# ConFLiCTuino.net
KiCad netlist of a schematic drawn in EAGLE
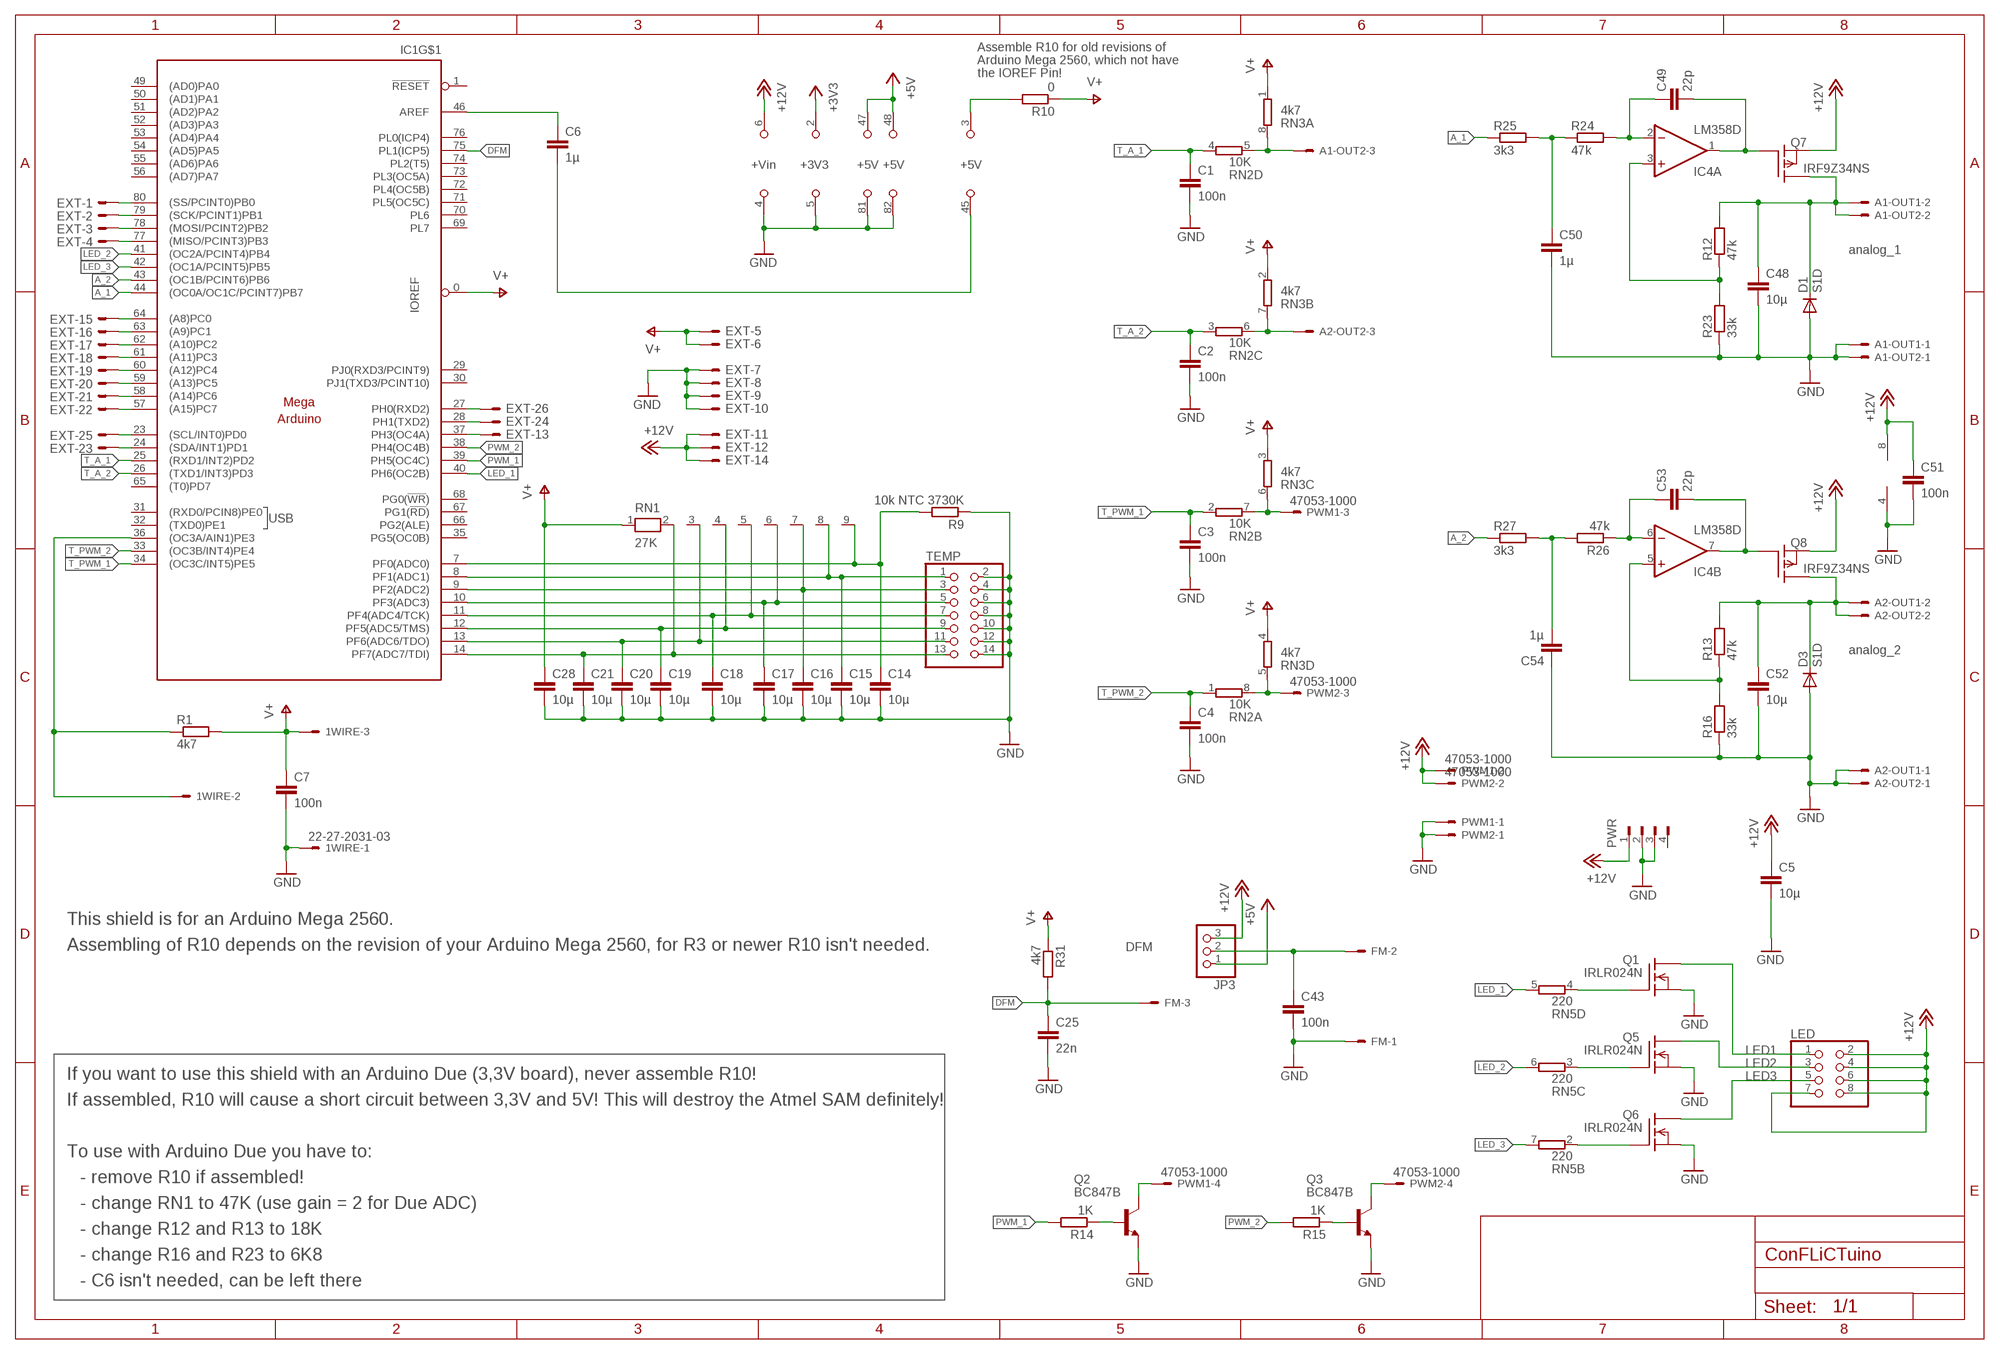
[diagram p0: schematic, sheet 1]

(export (version "E")
  (design (tool "Eeschema 10.0.6"))
  (components
    (comp (ref "1WIRE")
      (value "22-27-2031-03")
      (footprint "eagle-import:6410-03")
      (libsource (lib "eagle-import") (part "22-?-0327-2031"))
    )
    (comp (ref "A1-OUT1")
      (value "22-27-2031-03")
      (footprint "eagle-import:6410-03")
      (libsource (lib "eagle-import") (part "22-?-0327-2031"))
    )
    (comp (ref "A1-OUT2")
      (value "22-27-2031-03")
      (footprint "eagle-import:6410-03")
      (libsource (lib "eagle-import") (part "22-?-0327-2031"))
    )
    (comp (ref "A2-OUT1")
      (value "22-27-2031-03")
      (footprint "eagle-import:6410-03")
      (libsource (lib "eagle-import") (part "22-?-0327-2031"))
    )
    (comp (ref "A2-OUT2")
      (value "22-27-2031-03")
      (footprint "eagle-import:6410-03")
      (libsource (lib "eagle-import") (part "22-?-0327-2031"))
    )
    (comp (ref "C1")
      (value "100n")
      (footprint "eagle-import:C0805K")
      (libsource (lib "eagle-import") (part "C-EUC0805K"))
    )
    (comp (ref "C2")
      (value "100n")
      (footprint "eagle-import:C0805K")
      (libsource (lib "eagle-import") (part "C-EUC0805K"))
    )
    (comp (ref "C3")
      (value "100n")
      (footprint "eagle-import:C0805K")
      (libsource (lib "eagle-import") (part "C-EUC0805K"))
    )
    (comp (ref "C4")
      (value "100n")
      (footprint "eagle-import:C0805K")
      (libsource (lib "eagle-import") (part "C-EUC0805K"))
    )
    (comp (ref "C5")
      (value "10µ")
      (footprint "eagle-import:C0805K")
      (libsource (lib "eagle-import") (part "C-EUC0805K"))
    )
    (comp (ref "C6")
      (value "1µ")
      (footprint "eagle-import:C0805K")
      (libsource (lib "eagle-import") (part "C-EUC0805K"))
    )
    (comp (ref "C7")
      (value "100n")
      (footprint "eagle-import:C0805K")
      (libsource (lib "eagle-import") (part "C-EUC0805K"))
    )
    (comp (ref "C14")
      (value "10µ")
      (footprint "eagle-import:C0805K")
      (libsource (lib "eagle-import") (part "C-EUC0805K"))
    )
    (comp (ref "C15")
      (value "10µ")
      (footprint "eagle-import:C0805K")
      (libsource (lib "eagle-import") (part "C-EUC0805K"))
    )
    (comp (ref "C16")
      (value "10µ")
      (footprint "eagle-import:C0805K")
      (libsource (lib "eagle-import") (part "C-EUC0805K"))
    )
    (comp (ref "C17")
      (value "10µ")
      (footprint "eagle-import:C0805K")
      (libsource (lib "eagle-import") (part "C-EUC0805K"))
    )
    (comp (ref "C18")
      (value "10µ")
      (footprint "eagle-import:C0805K")
      (libsource (lib "eagle-import") (part "C-EUC0805K"))
    )
    (comp (ref "C19")
      (value "10µ")
      (footprint "eagle-import:C0805K")
      (libsource (lib "eagle-import") (part "C-EUC0805K"))
    )
    (comp (ref "C20")
      (value "10µ")
      (footprint "eagle-import:C0805K")
      (libsource (lib "eagle-import") (part "C-EUC0805K"))
    )
    (comp (ref "C21")
      (value "10µ")
      (footprint "eagle-import:C0805K")
      (libsource (lib "eagle-import") (part "C-EUC0805K"))
    )
    (comp (ref "C25")
      (value "22n")
      (footprint "eagle-import:C0805K")
      (libsource (lib "eagle-import") (part "C-EUC0805K"))
    )
    (comp (ref "C28")
      (value "10µ")
      (footprint "eagle-import:C0805K")
      (libsource (lib "eagle-import") (part "C-EUC0805K"))
    )
    (comp (ref "C43")
      (value "100n")
      (footprint "eagle-import:C0805K")
      (libsource (lib "eagle-import") (part "C-EUC0805K"))
    )
    (comp (ref "C48")
      (value "10µ")
      (footprint "eagle-import:C0805K")
      (libsource (lib "eagle-import") (part "C-EUC0805K"))
    )
    (comp (ref "C49")
      (value "22p")
      (footprint "eagle-import:C0805K")
      (libsource (lib "eagle-import") (part "C-EUC0805K"))
    )
    (comp (ref "C50")
      (value "1µ")
      (footprint "eagle-import:C0805K")
      (libsource (lib "eagle-import") (part "C-EUC0805K"))
    )
    (comp (ref "C51")
      (value "100n")
      (footprint "eagle-import:C0805K")
      (libsource (lib "eagle-import") (part "C-EUC0805K"))
    )
    (comp (ref "C52")
      (value "10µ")
      (footprint "eagle-import:C0805K")
      (libsource (lib "eagle-import") (part "C-EUC0805K"))
    )
    (comp (ref "C53")
      (value "22p")
      (footprint "eagle-import:C0805K")
      (libsource (lib "eagle-import") (part "C-EUC0805K"))
    )
    (comp (ref "C54")
      (value "1µ")
      (footprint "eagle-import:C0805K")
      (libsource (lib "eagle-import") (part "C-EUC0805K"))
    )
    (comp (ref "D1")
      (value "S1D")
      (footprint "eagle-import:DO214AC")
      (libsource (lib "eagle-import") (part "DIODE-DO214AC"))
    )
    (comp (ref "D3")
      (value "S1D")
      (footprint "eagle-import:DO214AC")
      (libsource (lib "eagle-import") (part "DIODE-DO214AC"))
    )
    (comp (ref "EXT")
      (value "ML26E")
      (footprint "eagle-import:ML26")
      (libsource (lib "eagle-import") (part "ML26E"))
    )
    (comp (ref "FM")
      (value "22-27-2031-03")
      (footprint "eagle-import:6410-03")
      (libsource (lib "eagle-import") (part "22-?-0327-2031"))
    )
    (comp (ref "IC1")
      (value "MEGAARDUINO_CUSTOM")
      (footprint "eagle-import:ARDUINO_MEGA_R3_SMALL_CUSTOM")
      (libsource (lib "eagle-import") (part "MEGAARDUINO_CUSTOM"))
    )
    (comp (ref "IC4")
      (value "LM358D")
      (footprint "eagle-import:SO08")
      (libsource (lib "eagle-import") (part "LM358D"))
    )
    (comp (ref "JP3")
      (value "PINHD-1X3")
      (footprint "eagle-import:1X03")
      (libsource (lib "eagle-import") (part "PINHD-1X3"))
    )
    (comp (ref "LED")
      (value "PINHD-2X4")
      (footprint "eagle-import:2X04")
      (libsource (lib "eagle-import") (part "PINHD-2X4"))
    )
    (comp (ref "PWM1")
      (value "47053-1000")
      (footprint "eagle-import:47053-1000")
      (libsource (lib "eagle-import") (part "47053-1000"))
    )
    (comp (ref "PWM2")
      (value "47053-1000")
      (footprint "eagle-import:47053-1000")
      (libsource (lib "eagle-import") (part "47053-1000"))
    )
    (comp (ref "PWR")
      (value "FLOPPY-4350211")
      (footprint "eagle-import:350211")
      (libsource (lib "eagle-import") (part "FLOPPY-4350211"))
    )
    (comp (ref "Q1")
      (value "IRLR024N")
      (footprint "eagle-import:DPACK")
      (libsource (lib "eagle-import") (part "IRLR024N"))
    )
    (comp (ref "Q2")
      (value "BC847B")
      (footprint "eagle-import:SOT23")
      (libsource (lib "eagle-import") (part "BC847SMDB"))
    )
    (comp (ref "Q3")
      (value "BC847B")
      (footprint "eagle-import:SOT23")
      (libsource (lib "eagle-import") (part "BC847SMDB"))
    )
    (comp (ref "Q5")
      (value "IRLR024N")
      (footprint "eagle-import:DPACK")
      (libsource (lib "eagle-import") (part "IRLR024N"))
    )
    (comp (ref "Q6")
      (value "IRLR024N")
      (footprint "eagle-import:DPACK")
      (libsource (lib "eagle-import") (part "IRLR024N"))
    )
    (comp (ref "Q7")
      (value "IRF9Z34NS")
      (footprint "eagle-import:D2PACK")
      (libsource (lib "eagle-import") (part "IRF9Z34NS"))
    )
    (comp (ref "Q8")
      (value "IRF9Z34NS")
      (footprint "eagle-import:D2PACK")
      (libsource (lib "eagle-import") (part "IRF9Z34NS"))
    )
    (comp (ref "R1")
      (value "4k7")
      (footprint "eagle-import:M0805")
      (libsource (lib "eagle-import") (part "R-EU_M0805"))
    )
    (comp (ref "R9")
      (value "10k NTC 3730K")
      (footprint "eagle-import:M0805")
      (libsource (lib "eagle-import") (part "R-EU_M0805"))
    )
    (comp (ref "R10")
      (value "0")
      (footprint "eagle-import:M0805")
      (libsource (lib "eagle-import") (part "R-EU_M0805"))
    )
    (comp (ref "R12")
      (value "47k")
      (footprint "eagle-import:M0805")
      (libsource (lib "eagle-import") (part "R-EU_M0805"))
    )
    (comp (ref "R13")
      (value "47k")
      (footprint "eagle-import:M0805")
      (libsource (lib "eagle-import") (part "R-EU_M0805"))
    )
    (comp (ref "R14")
      (value "1K")
      (footprint "eagle-import:M0805")
      (libsource (lib "eagle-import") (part "R-EU_M0805"))
    )
    (comp (ref "R15")
      (value "1K")
      (footprint "eagle-import:M0805")
      (libsource (lib "eagle-import") (part "R-EU_M0805"))
    )
    (comp (ref "R16")
      (value "33k")
      (footprint "eagle-import:M0805")
      (libsource (lib "eagle-import") (part "R-EU_M0805"))
    )
    (comp (ref "R23")
      (value "33k")
      (footprint "eagle-import:M0805")
      (libsource (lib "eagle-import") (part "R-EU_M0805"))
    )
    (comp (ref "R24")
      (value "47k")
      (footprint "eagle-import:M0805")
      (libsource (lib "eagle-import") (part "R-EU_M0805"))
    )
    (comp (ref "R25")
      (value "3k3")
      (footprint "eagle-import:M0805")
      (libsource (lib "eagle-import") (part "R-EU_M0805"))
    )
    (comp (ref "R26")
      (value "47k")
      (footprint "eagle-import:M0805")
      (libsource (lib "eagle-import") (part "R-EU_M0805"))
    )
    (comp (ref "R27")
      (value "3k3")
      (footprint "eagle-import:M0805")
      (libsource (lib "eagle-import") (part "R-EU_M0805"))
    )
    (comp (ref "R31")
      (value "4k7")
      (footprint "eagle-import:M0805")
      (libsource (lib "eagle-import") (part "R-EU_M0805"))
    )
    (comp (ref "RN1")
      (value "27K")
      (footprint "eagle-import:RN-9")
      (libsource (lib "eagle-import") (part "RN08"))
    )
    (comp (ref "RN2")
      (value "10K")
      (footprint "eagle-import:CAT16")
      (libsource (lib "eagle-import") (part "4R-NCAT16"))
    )
    (comp (ref "RN3")
      (value "4k7")
      (footprint "eagle-import:CAT16")
      (libsource (lib "eagle-import") (part "4R-NCAT16"))
    )
    (comp (ref "RN5")
      (value "220")
      (footprint "eagle-import:CAT16")
      (libsource (lib "eagle-import") (part "4R-NCAT16"))
    )
    (comp (ref "TEMP")
      (value "PINHD-2X7")
      (footprint "eagle-import:2X07")
      (libsource (lib "eagle-import") (part "PINHD-2X7"))
    )
  )
  (nets
    (net (code "1") (name "+3V3") (class "Default")
      (node (ref "IC1") (pin "2") (pinfunction "+3V3_2") (pintype "power_in"))
    )
    (net (code "2") (name "+5V") (class "Default")
      (node (ref "IC1") (pin "47") (pinfunction "+5V_47") (pintype "power_in"))
      (node (ref "IC1") (pin "48") (pinfunction "+5V_48") (pintype "power_in"))
      (node (ref "JP3") (pin "1") (pinfunction "1_1") (pintype "passive"))
    )
    (net (code "3") (name "+12V") (class "Default")
      (node (ref "C5") (pin "1") (pinfunction "1_1") (pintype "passive"))
      (node (ref "C51") (pin "1") (pinfunction "1_1") (pintype "passive"))
      (node (ref "EXT") (pin "11") (pinfunction "S_11") (pintype "passive"))
      (node (ref "EXT") (pin "12") (pinfunction "S_12") (pintype "passive"))
      (node (ref "EXT") (pin "14") (pinfunction "S_14") (pintype "passive"))
      (node (ref "IC1") (pin "6") (pinfunction "+VIN_6") (pintype "power_in"))
      (node (ref "IC4") (pin "8") (pinfunction "V+_8") (pintype "power_in"))
      (node (ref "JP3") (pin "3") (pinfunction "3_3") (pintype "passive"))
      (node (ref "LED") (pin "2") (pinfunction "2_2") (pintype "passive"))
      (node (ref "LED") (pin "4") (pinfunction "4_4") (pintype "passive"))
      (node (ref "LED") (pin "6") (pinfunction "6_6") (pintype "passive"))
      (node (ref "LED") (pin "7") (pinfunction "7_7") (pintype "passive"))
      (node (ref "LED") (pin "8") (pinfunction "8_8") (pintype "passive"))
      (node (ref "PWM1") (pin "2") (pinfunction "S_2") (pintype "passive"))
      (node (ref "PWM2") (pin "2") (pinfunction "S_2") (pintype "passive"))
      (node (ref "PWR") (pin "1") (pinfunction "1_1") (pintype "passive"))
      (node (ref "Q7") (pin "3") (pinfunction "S_3") (pintype "passive"))
      (node (ref "Q8") (pin "3") (pinfunction "S_3") (pintype "passive"))
    )
    (net (code "4") (name "/LED1") (class "Default")
      (node (ref "LED") (pin "1") (pinfunction "1_1") (pintype "passive"))
      (node (ref "Q1") (pin "4") (pinfunction "D_4") (pintype "passive"))
    )
    (net (code "5") (name "/LED2") (class "Default")
      (node (ref "LED") (pin "3") (pinfunction "3_3") (pintype "passive"))
      (node (ref "Q5") (pin "4") (pinfunction "D_4") (pintype "passive"))
    )
    (net (code "6") (name "/LED3") (class "Default")
      (node (ref "LED") (pin "5") (pinfunction "5_5") (pintype "passive"))
      (node (ref "Q6") (pin "4") (pinfunction "D_4") (pintype "passive"))
    )
    (net (code "7") (name "A_1") (class "Default")
      (node (ref "IC1") (pin "44") (pinfunction "(OC0A/OC1C/PCINT7)PB7_44") (pintype "bidirectional"))
      (node (ref "R25") (pin "1") (pinfunction "1_1") (pintype "passive"))
    )
    (net (code "8") (name "A_2") (class "Default")
      (node (ref "IC1") (pin "43") (pinfunction "(OC1B/PCINT6)PB6_43") (pintype "bidirectional"))
      (node (ref "R27") (pin "1") (pinfunction "1_1") (pintype "passive"))
    )
    (net (code "9") (name "DFM") (class "Default")
      (node (ref "C25") (pin "1") (pinfunction "1_1") (pintype "passive"))
      (node (ref "FM") (pin "3") (pinfunction "S_3") (pintype "passive"))
      (node (ref "IC1") (pin "75") (pinfunction "PL1(ICP5)_75") (pintype "bidirectional"))
      (node (ref "R31") (pin "2") (pinfunction "2_2") (pintype "passive"))
    )
    (net (code "10") (name "GND") (class "Default")
      (node (ref "1WIRE") (pin "1") (pinfunction "S_1") (pintype "passive"))
      (node (ref "A1-OUT1") (pin "1") (pinfunction "S_1") (pintype "passive"))
      (node (ref "A1-OUT2") (pin "1") (pinfunction "S_1") (pintype "passive"))
      (node (ref "A2-OUT1") (pin "1") (pinfunction "S_1") (pintype "passive"))
      (node (ref "A2-OUT2") (pin "1") (pinfunction "S_1") (pintype "passive"))
      (node (ref "C1") (pin "2") (pinfunction "2_2") (pintype "passive"))
      (node (ref "C14") (pin "2") (pinfunction "2_2") (pintype "passive"))
      (node (ref "C15") (pin "2") (pinfunction "2_2") (pintype "passive"))
      (node (ref "C16") (pin "2") (pinfunction "2_2") (pintype "passive"))
      (node (ref "C17") (pin "2") (pinfunction "2_2") (pintype "passive"))
      (node (ref "C18") (pin "2") (pinfunction "2_2") (pintype "passive"))
      (node (ref "C19") (pin "2") (pinfunction "2_2") (pintype "passive"))
      (node (ref "C2") (pin "2") (pinfunction "2_2") (pintype "passive"))
      (node (ref "C20") (pin "2") (pinfunction "2_2") (pintype "passive"))
      (node (ref "C21") (pin "2") (pinfunction "2_2") (pintype "passive"))
      (node (ref "C25") (pin "2") (pinfunction "2_2") (pintype "passive"))
      (node (ref "C28") (pin "2") (pinfunction "2_2") (pintype "passive"))
      (node (ref "C3") (pin "2") (pinfunction "2_2") (pintype "passive"))
      (node (ref "C4") (pin "2") (pinfunction "2_2") (pintype "passive"))
      (node (ref "C43") (pin "2") (pinfunction "2_2") (pintype "passive"))
      (node (ref "C48") (pin "2") (pinfunction "2_2") (pintype "passive"))
      (node (ref "C5") (pin "2") (pinfunction "2_2") (pintype "passive"))
      (node (ref "C50") (pin "2") (pinfunction "2_2") (pintype "passive"))
      (node (ref "C51") (pin "2") (pinfunction "2_2") (pintype "passive"))
      (node (ref "C52") (pin "2") (pinfunction "2_2") (pintype "passive"))
      (node (ref "C54") (pin "1") (pinfunction "1_1") (pintype "passive"))
      (node (ref "C7") (pin "2") (pinfunction "2_2") (pintype "passive"))
      (node (ref "D1") (pin "A") (pinfunction "A_A") (pintype "passive"))
      (node (ref "D3") (pin "A") (pinfunction "A_A") (pintype "passive"))
      (node (ref "EXT") (pin "10") (pinfunction "S_10") (pintype "passive"))
      (node (ref "EXT") (pin "7") (pinfunction "S_7") (pintype "passive"))
      (node (ref "EXT") (pin "8") (pinfunction "S_8") (pintype "passive"))
      (node (ref "EXT") (pin "9") (pinfunction "S_9") (pintype "passive"))
      (node (ref "FM") (pin "1") (pinfunction "S_1") (pintype "passive"))
      (node (ref "IC1") (pin "4") (pinfunction "GND_4") (pintype "power_in"))
      (node (ref "IC1") (pin "5") (pinfunction "GND_5") (pintype "power_in"))
      (node (ref "IC1") (pin "81") (pinfunction "GND_81") (pintype "power_in"))
      (node (ref "IC1") (pin "82") (pinfunction "GND_82") (pintype "power_in"))
      (node (ref "IC4") (pin "4") (pinfunction "V-_4") (pintype "power_in"))
      (node (ref "PWM1") (pin "1") (pinfunction "S_1") (pintype "passive"))
      (node (ref "PWM2") (pin "1") (pinfunction "S_1") (pintype "passive"))
      (node (ref "PWR") (pin "2") (pinfunction "2_2") (pintype "passive"))
      (node (ref "PWR") (pin "3") (pinfunction "3_3") (pintype "passive"))
      (node (ref "Q1") (pin "3") (pinfunction "S_3") (pintype "passive"))
      (node (ref "Q2") (pin "2") (pinfunction "E_2") (pintype "passive"))
      (node (ref "Q3") (pin "2") (pinfunction "E_2") (pintype "passive"))
      (node (ref "Q5") (pin "3") (pinfunction "S_3") (pintype "passive"))
      (node (ref "Q6") (pin "3") (pinfunction "S_3") (pintype "passive"))
      (node (ref "R16") (pin "1") (pinfunction "1_1") (pintype "passive"))
      (node (ref "R23") (pin "1") (pinfunction "1_1") (pintype "passive"))
      (node (ref "R9") (pin "1") (pinfunction "1_1") (pintype "passive"))
      (node (ref "TEMP") (pin "10") (pinfunction "10_10") (pintype "passive"))
      (node (ref "TEMP") (pin "12") (pinfunction "12_12") (pintype "passive"))
      (node (ref "TEMP") (pin "14") (pinfunction "14_14") (pintype "passive"))
      (node (ref "TEMP") (pin "2") (pinfunction "2_2") (pintype "passive"))
      (node (ref "TEMP") (pin "4") (pinfunction "4_4") (pintype "passive"))
      (node (ref "TEMP") (pin "6") (pinfunction "6_6") (pintype "passive"))
      (node (ref "TEMP") (pin "8") (pinfunction "8_8") (pintype "passive"))
    )
    (net (code "11") (name "LED_1") (class "Default")
      (node (ref "IC1") (pin "40") (pinfunction "PH6(OC2B)_40") (pintype "bidirectional"))
      (node (ref "RN5") (pin "5") (pinfunction "2_5") (pintype "passive"))
    )
    (net (code "12") (name "LED_2") (class "Default")
      (node (ref "IC1") (pin "41") (pinfunction "(OC2A/PCINT4)PB4_41") (pintype "bidirectional"))
      (node (ref "RN5") (pin "6") (pinfunction "2_6") (pintype "passive"))
    )
    (net (code "13") (name "LED_3") (class "Default")
      (node (ref "IC1") (pin "42") (pinfunction "(OC1A/PCINT5)PB5_42") (pintype "bidirectional"))
      (node (ref "RN5") (pin "7") (pinfunction "2_7") (pintype "passive"))
    )
    (net (code "14") (name "Net-(1WIREB-S)") (class "Default")
      (node (ref "1WIRE") (pin "2") (pinfunction "S_2") (pintype "passive"))
      (node (ref "IC1") (pin "36") (pinfunction "(OC3A/AIN1)PE3_36") (pintype "bidirectional"))
      (node (ref "R1") (pin "1") (pinfunction "1_1") (pintype "passive"))
    )
    (net (code "15") (name "Net-(A1-OUT1B-S)") (class "Default")
      (node (ref "A1-OUT1") (pin "2") (pinfunction "S_2") (pintype "passive"))
      (node (ref "A1-OUT2") (pin "2") (pinfunction "S_2") (pintype "passive"))
      (node (ref "C48") (pin "1") (pinfunction "1_1") (pintype "passive"))
      (node (ref "D1") (pin "C") (pinfunction "C_C") (pintype "passive"))
      (node (ref "Q7") (pin "2") (pinfunction "D_2") (pintype "passive"))
      (node (ref "R12") (pin "2") (pinfunction "2_2") (pintype "passive"))
    )
    (net (code "16") (name "Net-(A1-OUT2C-S)") (class "Default")
      (node (ref "A1-OUT2") (pin "3") (pinfunction "S_3") (pintype "passive"))
      (node (ref "RN2") (pin "5") (pinfunction "2_5") (pintype "passive"))
      (node (ref "RN3") (pin "8") (pinfunction "2_8") (pintype "passive"))
    )
    (net (code "17") (name "Net-(A2-OUT1B-S)") (class "Default")
      (node (ref "A2-OUT1") (pin "2") (pinfunction "S_2") (pintype "passive"))
      (node (ref "A2-OUT2") (pin "2") (pinfunction "S_2") (pintype "passive"))
      (node (ref "C52") (pin "1") (pinfunction "1_1") (pintype "passive"))
      (node (ref "D3") (pin "C") (pinfunction "C_C") (pintype "passive"))
      (node (ref "Q8") (pin "2") (pinfunction "D_2") (pintype "passive"))
      (node (ref "R13") (pin "2") (pinfunction "2_2") (pintype "passive"))
    )
    (net (code "18") (name "Net-(A2-OUT2C-S)") (class "Default")
      (node (ref "A2-OUT2") (pin "3") (pinfunction "S_3") (pintype "passive"))
      (node (ref "RN2") (pin "6") (pinfunction "2_6") (pintype "passive"))
      (node (ref "RN3") (pin "7") (pinfunction "2_7") (pintype "passive"))
    )
    (net (code "19") (name "Net-(C50-Pad1)") (class "Default")
      (node (ref "C50") (pin "1") (pinfunction "1_1") (pintype "passive"))
      (node (ref "R24") (pin "1") (pinfunction "1_1") (pintype "passive"))
      (node (ref "R25") (pin "2") (pinfunction "2_2") (pintype "passive"))
    )
    (net (code "20") (name "Net-(C54-Pad2)") (class "Default")
      (node (ref "C54") (pin "2") (pinfunction "2_2") (pintype "passive"))
      (node (ref "R26") (pin "2") (pinfunction "2_2") (pintype "passive"))
      (node (ref "R27") (pin "2") (pinfunction "2_2") (pintype "passive"))
    )
    (net (code "21") (name "Net-(EXTA-S)") (class "Default")
      (node (ref "EXT") (pin "1") (pinfunction "S_1") (pintype "passive"))
      (node (ref "IC1") (pin "80") (pinfunction "(SS/PCINT0)PB0_80") (pintype "bidirectional"))
    )
    (net (code "22") (name "Net-(EXTE-S)") (class "Default")
      (node (ref "EXT") (pin "13") (pinfunction "S_13") (pintype "passive"))
      (node (ref "IC1") (pin "37") (pinfunction "PH3(OC4A)_37") (pintype "bidirectional"))
    )
    (net (code "23") (name "Net-(EXTG-S)") (class "Default")
      (node (ref "EXT") (pin "15") (pinfunction "S_15") (pintype "passive"))
      (node (ref "IC1") (pin "64") (pinfunction "(A8)PC0_64") (pintype "bidirectional"))
    )
    (net (code "24") (name "Net-(EXTH-S)") (class "Default")
      (node (ref "EXT") (pin "16") (pinfunction "S_16") (pintype "passive"))
      (node (ref "IC1") (pin "63") (pinfunction "(A9)PC1_63") (pintype "bidirectional"))
    )
    (net (code "25") (name "Net-(EXTI-S)") (class "Default")
      (node (ref "EXT") (pin "17") (pinfunction "S_17") (pintype "passive"))
      (node (ref "IC1") (pin "62") (pinfunction "(A10)PC2_62") (pintype "bidirectional"))
    )
    (net (code "26") (name "Net-(EXTJ-S)") (class "Default")
      (node (ref "EXT") (pin "18") (pinfunction "S_18") (pintype "passive"))
      (node (ref "IC1") (pin "61") (pinfunction "(A11)PC3_61") (pintype "bidirectional"))
    )
    (net (code "27") (name "Net-(EXTK-S)") (class "Default")
      (node (ref "EXT") (pin "19") (pinfunction "S_19") (pintype "passive"))
      (node (ref "IC1") (pin "60") (pinfunction "(A12)PC4_60") (pintype "bidirectional"))
    )
    (net (code "28") (name "Net-(EXTL-S)") (class "Default")
      (node (ref "EXT") (pin "2") (pinfunction "S_2") (pintype "passive"))
      (node (ref "IC1") (pin "79") (pinfunction "(SCK/PCINT1)PB1_79") (pintype "bidirectional"))
    )
    (net (code "29") (name "Net-(EXTM-S)") (class "Default")
      (node (ref "EXT") (pin "20") (pinfunction "S_20") (pintype "passive"))
      (node (ref "IC1") (pin "59") (pinfunction "(A13)PC5_59") (pintype "bidirectional"))
    )
    (net (code "30") (name "Net-(EXTN-S)") (class "Default")
      (node (ref "EXT") (pin "21") (pinfunction "S_21") (pintype "passive"))
      (node (ref "IC1") (pin "58") (pinfunction "(A14)PC6_58") (pintype "bidirectional"))
    )
    (net (code "31") (name "Net-(EXTO-S)") (class "Default")
      (node (ref "EXT") (pin "22") (pinfunction "S_22") (pintype "passive"))
      (node (ref "IC1") (pin "57") (pinfunction "(A15)PC7_57") (pintype "bidirectional"))
    )
    (net (code "32") (name "Net-(EXTP-S)") (class "Default")
      (node (ref "EXT") (pin "23") (pinfunction "S_23") (pintype "passive"))
      (node (ref "IC1") (pin "24") (pinfunction "(SDA/INT1)PD1_24") (pintype "bidirectional"))
    )
    (net (code "33") (name "Net-(EXTQ-S)") (class "Default")
      (node (ref "EXT") (pin "24") (pinfunction "S_24") (pintype "passive"))
      (node (ref "IC1") (pin "28") (pinfunction "PH1(TXD2)_28") (pintype "bidirectional"))
    )
    (net (code "34") (name "Net-(EXTR-S)") (class "Default")
      (node (ref "EXT") (pin "25") (pinfunction "S_25") (pintype "passive"))
      (node (ref "IC1") (pin "23") (pinfunction "(SCL/INT0)PD0_23") (pintype "bidirectional"))
    )
    (net (code "35") (name "Net-(EXTS-S)") (class "Default")
      (node (ref "EXT") (pin "26") (pinfunction "S_26") (pintype "passive"))
      (node (ref "IC1") (pin "27") (pinfunction "PH0(RXD2)_27") (pintype "bidirectional"))
    )
    (net (code "36") (name "Net-(EXTT-S)") (class "Default")
      (node (ref "EXT") (pin "3") (pinfunction "S_3") (pintype "passive"))
      (node (ref "IC1") (pin "78") (pinfunction "(MOSI/PCINT2)PB2_78") (pintype "bidirectional"))
    )
    (net (code "37") (name "Net-(EXTU-S)") (class "Default")
      (node (ref "EXT") (pin "4") (pinfunction "S_4") (pintype "passive"))
      (node (ref "IC1") (pin "77") (pinfunction "(MISO/PCINT3)PB3_77") (pintype "bidirectional"))
    )
    (net (code "38") (name "Net-(FMB-S)") (class "Default")
      (node (ref "C43") (pin "1") (pinfunction "1_1") (pintype "passive"))
      (node (ref "FM") (pin "2") (pinfunction "S_2") (pintype "passive"))
      (node (ref "JP3") (pin "2") (pinfunction "2_2") (pintype "passive"))
    )
    (net (code "39") (name "Net-(IC1A-AREF)") (class "Default")
      (node (ref "C6") (pin "1") (pinfunction "1_1") (pintype "passive"))
      (node (ref "IC1") (pin "46") (pinfunction "AREF_46") (pintype "bidirectional"))
    )
    (net (code "40") (name "Net-(IC1A-PF0(ADC0))") (class "Default")
      (node (ref "C14") (pin "1") (pinfunction "1_1") (pintype "passive"))
      (node (ref "IC1") (pin "7") (pinfunction "PF0(ADC0)_7") (pintype "bidirectional"))
      (node (ref "R9") (pin "2") (pinfunction "2_2") (pintype "passive"))
      (node (ref "RN1") (pin "9") (pinfunction "9_9") (pintype "passive"))
    )
    (net (code "41") (name "Net-(IC1A-PF1(ADC1))") (class "Default")
      (node (ref "C15") (pin "1") (pinfunction "1_1") (pintype "passive"))
      (node (ref "IC1") (pin "8") (pinfunction "PF1(ADC1)_8") (pintype "bidirectional"))
      (node (ref "RN1") (pin "8") (pinfunction "8_8") (pintype "passive"))
      (node (ref "TEMP") (pin "1") (pinfunction "1_1") (pintype "passive"))
    )
    (net (code "42") (name "Net-(IC1A-PF2(ADC2))") (class "Default")
      (node (ref "C16") (pin "1") (pinfunction "1_1") (pintype "passive"))
      (node (ref "IC1") (pin "9") (pinfunction "PF2(ADC2)_9") (pintype "bidirectional"))
      (node (ref "RN1") (pin "7") (pinfunction "7_7") (pintype "passive"))
      (node (ref "TEMP") (pin "3") (pinfunction "3_3") (pintype "passive"))
    )
    (net (code "43") (name "Net-(IC1A-PF3(ADC3))") (class "Default")
      (node (ref "C17") (pin "1") (pinfunction "1_1") (pintype "passive"))
      (node (ref "IC1") (pin "10") (pinfunction "PF3(ADC3)_10") (pintype "bidirectional"))
      (node (ref "RN1") (pin "6") (pinfunction "6_6") (pintype "passive"))
      (node (ref "TEMP") (pin "5") (pinfunction "5_5") (pintype "passive"))
    )
    (net (code "44") (name "Net-(IC1A-PF4(ADC4{slash}TCK))") (class "Default")
      (node (ref "C18") (pin "1") (pinfunction "1_1") (pintype "passive"))
      (node (ref "IC1") (pin "11") (pinfunction "PF4(ADC4/TCK)_11") (pintype "bidirectional"))
      (node (ref "RN1") (pin "5") (pinfunction "5_5") (pintype "passive"))
      (node (ref "TEMP") (pin "7") (pinfunction "7_7") (pintype "passive"))
    )
    (net (code "45") (name "Net-(IC1A-PF5(ADC5{slash}TMS))") (class "Default")
      (node (ref "C19") (pin "1") (pinfunction "1_1") (pintype "passive"))
      (node (ref "IC1") (pin "12") (pinfunction "PF5(ADC5/TMS)_12") (pintype "bidirectional"))
      (node (ref "RN1") (pin "4") (pinfunction "4_4") (pintype "passive"))
      (node (ref "TEMP") (pin "9") (pinfunction "9_9") (pintype "passive"))
    )
    (net (code "46") (name "Net-(IC1A-PF6(ADC6{slash}TDO))") (class "Default")
      (node (ref "C20") (pin "1") (pinfunction "1_1") (pintype "passive"))
      (node (ref "IC1") (pin "13") (pinfunction "PF6(ADC6/TDO)_13") (pintype "bidirectional"))
      (node (ref "RN1") (pin "3") (pinfunction "3_3") (pintype "passive"))
      (node (ref "TEMP") (pin "11") (pinfunction "11_11") (pintype "passive"))
    )
    (net (code "47") (name "Net-(IC1A-PF7(ADC7{slash}TDI))") (class "Default")
      (node (ref "C21") (pin "1") (pinfunction "1_1") (pintype "passive"))
      (node (ref "IC1") (pin "14") (pinfunction "PF7(ADC7/TDI)_14") (pintype "bidirectional"))
      (node (ref "RN1") (pin "2") (pinfunction "2_2") (pintype "passive"))
      (node (ref "TEMP") (pin "13") (pinfunction "13_13") (pintype "passive"))
    )
    (net (code "48") (name "Net-(IC1E-+5V)") (class "Default")
      (node (ref "IC1") (pin "3") (pinfunction "+5V_3") (pintype "power_in"))
      (node (ref "R10") (pin "2") (pinfunction "2_2") (pintype "passive"))
    )
    (net (code "49") (name "Net-(IC1E-GND)") (class "Default")
      (node (ref "C6") (pin "2") (pinfunction "2_2") (pintype "passive"))
      (node (ref "IC1") (pin "45") (pinfunction "GND_45") (pintype "power_in"))
    )
    (net (code "50") (name "Net-(IC4A-+IN)") (class "Default")
      (node (ref "IC4") (pin "3") (pinfunction "+IN_3") (pintype "input"))
      (node (ref "R12") (pin "1") (pinfunction "1_1") (pintype "passive"))
      (node (ref "R23") (pin "2") (pinfunction "2_2") (pintype "passive"))
    )
    (net (code "51") (name "Net-(IC4A--IN)") (class "Default")
      (node (ref "C49") (pin "1") (pinfunction "1_1") (pintype "passive"))
      (node (ref "IC4") (pin "2") (pinfunction "-IN_2") (pintype "input"))
      (node (ref "R24") (pin "2") (pinfunction "2_2") (pintype "passive"))
    )
    (net (code "52") (name "Net-(IC4A-OUT)") (class "Default")
      (node (ref "C49") (pin "2") (pinfunction "2_2") (pintype "passive"))
      (node (ref "IC4") (pin "1") (pinfunction "OUT_1") (pintype "output"))
      (node (ref "Q7") (pin "1") (pinfunction "G_1") (pintype "passive"))
    )
    (net (code "53") (name "Net-(IC4B-+IN)") (class "Default")
      (node (ref "IC4") (pin "5") (pinfunction "+IN_5") (pintype "input"))
      (node (ref "R13") (pin "1") (pinfunction "1_1") (pintype "passive"))
      (node (ref "R16") (pin "2") (pinfunction "2_2") (pintype "passive"))
    )
    (net (code "54") (name "Net-(IC4B--IN)") (class "Default")
      (node (ref "C53") (pin "1") (pinfunction "1_1") (pintype "passive"))
      (node (ref "IC4") (pin "6") (pinfunction "-IN_6") (pintype "input"))
      (node (ref "R26") (pin "1") (pinfunction "1_1") (pintype "passive"))
    )
    (net (code "55") (name "Net-(IC4B-OUT)") (class "Default")
      (node (ref "C53") (pin "2") (pinfunction "2_2") (pintype "passive"))
      (node (ref "IC4") (pin "7") (pinfunction "OUT_7") (pintype "output"))
      (node (ref "Q8") (pin "1") (pinfunction "G_1") (pintype "passive"))
    )
    (net (code "56") (name "Net-(PWM1C-S)") (class "Default")
      (node (ref "PWM1") (pin "3") (pinfunction "S_3") (pintype "passive"))
      (node (ref "RN2") (pin "7") (pinfunction "2_7") (pintype "passive"))
      (node (ref "RN3") (pin "6") (pinfunction "2_6") (pintype "passive"))
    )
    (net (code "57") (name "Net-(PWM1D-S)") (class "Default")
      (node (ref "PWM1") (pin "4") (pinfunction "S_4") (pintype "passive"))
      (node (ref "Q2") (pin "3") (pinfunction "C_3") (pintype "passive"))
    )
    (net (code "58") (name "Net-(PWM2C-S)") (class "Default")
      (node (ref "PWM2") (pin "3") (pinfunction "S_3") (pintype "passive"))
      (node (ref "RN2") (pin "8") (pinfunction "2_8") (pintype "passive"))
      (node (ref "RN3") (pin "5") (pinfunction "2_5") (pintype "passive"))
    )
    (net (code "59") (name "Net-(PWM2D-S)") (class "Default")
      (node (ref "PWM2") (pin "4") (pinfunction "S_4") (pintype "passive"))
      (node (ref "Q3") (pin "3") (pinfunction "C_3") (pintype "passive"))
    )
    (net (code "60") (name "Net-(Q1-G)") (class "Default")
      (node (ref "Q1") (pin "1") (pinfunction "G_1") (pintype "passive"))
      (node (ref "RN5") (pin "4") (pinfunction "1_4") (pintype "passive"))
    )
    (net (code "61") (name "Net-(Q2-B)") (class "Default")
      (node (ref "Q2") (pin "1") (pinfunction "B_1") (pintype "passive"))
      (node (ref "R14") (pin "1") (pinfunction "1_1") (pintype "passive"))
    )
    (net (code "62") (name "Net-(Q3-B)") (class "Default")
      (node (ref "Q3") (pin "1") (pinfunction "B_1") (pintype "passive"))
      (node (ref "R15") (pin "1") (pinfunction "1_1") (pintype "passive"))
    )
    (net (code "63") (name "Net-(Q5-G)") (class "Default")
      (node (ref "Q5") (pin "1") (pinfunction "G_1") (pintype "passive"))
      (node (ref "RN5") (pin "3") (pinfunction "1_3") (pintype "passive"))
    )
    (net (code "64") (name "Net-(Q6-G)") (class "Default")
      (node (ref "Q6") (pin "1") (pinfunction "G_1") (pintype "passive"))
      (node (ref "RN5") (pin "2") (pinfunction "1_2") (pintype "passive"))
    )
    (net (code "65") (name "PWM_1") (class "Default")
      (node (ref "IC1") (pin "39") (pinfunction "PH5(OC4C)_39") (pintype "bidirectional"))
      (node (ref "R14") (pin "2") (pinfunction "2_2") (pintype "passive"))
    )
    (net (code "66") (name "PWM_2") (class "Default")
      (node (ref "IC1") (pin "38") (pinfunction "PH4(OC4B)_38") (pintype "bidirectional"))
      (node (ref "R15") (pin "2") (pinfunction "2_2") (pintype "passive"))
    )
    (net (code "67") (name "T_A_1") (class "Default")
      (node (ref "C1") (pin "1") (pinfunction "1_1") (pintype "passive"))
      (node (ref "IC1") (pin "25") (pinfunction "(RXD1/INT2)PD2_25") (pintype "bidirectional"))
      (node (ref "RN2") (pin "4") (pinfunction "1_4") (pintype "passive"))
    )
    (net (code "68") (name "T_A_2") (class "Default")
      (node (ref "C2") (pin "1") (pinfunction "1_1") (pintype "passive"))
      (node (ref "IC1") (pin "26") (pinfunction "(TXD1/INT3)PD3_26") (pintype "bidirectional"))
      (node (ref "RN2") (pin "3") (pinfunction "1_3") (pintype "passive"))
    )
    (net (code "69") (name "T_PWM_1") (class "Default")
      (node (ref "C3") (pin "1") (pinfunction "1_1") (pintype "passive"))
      (node (ref "IC1") (pin "34") (pinfunction "(OC3C/INT5)PE5_34") (pintype "bidirectional"))
      (node (ref "RN2") (pin "2") (pinfunction "1_2") (pintype "passive"))
    )
    (net (code "70") (name "T_PWM_2") (class "Default")
      (node (ref "C4") (pin "1") (pinfunction "1_1") (pintype "passive"))
      (node (ref "IC1") (pin "33") (pinfunction "(OC3B/INT4)PE4_33") (pintype "bidirectional"))
      (node (ref "RN2") (pin "1") (pinfunction "1_1") (pintype "passive"))
    )
    (net (code "71") (name "V+") (class "Default")
      (node (ref "1WIRE") (pin "3") (pinfunction "S_3") (pintype "passive"))
      (node (ref "C28") (pin "1") (pinfunction "1_1") (pintype "passive"))
      (node (ref "C7") (pin "1") (pinfunction "1_1") (pintype "passive"))
      (node (ref "EXT") (pin "5") (pinfunction "S_5") (pintype "passive"))
      (node (ref "EXT") (pin "6") (pinfunction "S_6") (pintype "passive"))
      (node (ref "IC1") (pin "0") (pinfunction "IOREF_0") (pintype "power_in"))
      (node (ref "R1") (pin "2") (pinfunction "2_2") (pintype "passive"))
      (node (ref "R10") (pin "1") (pinfunction "1_1") (pintype "passive"))
      (node (ref "R31") (pin "1") (pinfunction "1_1") (pintype "passive"))
      (node (ref "RN1") (pin "1") (pinfunction "1_1") (pintype "passive"))
      (node (ref "RN3") (pin "1") (pinfunction "1_1") (pintype "passive"))
      (node (ref "RN3") (pin "2") (pinfunction "1_2") (pintype "passive"))
      (node (ref "RN3") (pin "3") (pinfunction "1_3") (pintype "passive"))
      (node (ref "RN3") (pin "4") (pinfunction "1_4") (pintype "passive"))
    )
    (net (code "72") (name "unconnected-(IC1A-(AD0)PA0-Pad49)") (class "Default")
      (node (ref "IC1") (pin "49") (pinfunction "(AD0)PA0_49") (pintype "bidirectional"))
    )
    (net (code "73") (name "unconnected-(IC1A-(AD1)PA1-Pad50)") (class "Default")
      (node (ref "IC1") (pin "50") (pinfunction "(AD1)PA1_50") (pintype "bidirectional"))
    )
    (net (code "74") (name "unconnected-(IC1A-(AD2)PA2-Pad51)") (class "Default")
      (node (ref "IC1") (pin "51") (pinfunction "(AD2)PA2_51") (pintype "bidirectional"))
    )
    (net (code "75") (name "unconnected-(IC1A-(AD3)PA3-Pad52)") (class "Default")
      (node (ref "IC1") (pin "52") (pinfunction "(AD3)PA3_52") (pintype "bidirectional"))
    )
    (net (code "76") (name "unconnected-(IC1A-(AD4)PA4-Pad53)") (class "Default")
      (node (ref "IC1") (pin "53") (pinfunction "(AD4)PA4_53") (pintype "bidirectional"))
    )
    (net (code "77") (name "unconnected-(IC1A-(AD5)PA5-Pad54)") (class "Default")
      (node (ref "IC1") (pin "54") (pinfunction "(AD5)PA5_54") (pintype "bidirectional"))
    )
    (net (code "78") (name "unconnected-(IC1A-(AD6)PA6-Pad55)") (class "Default")
      (node (ref "IC1") (pin "55") (pinfunction "(AD6)PA6_55") (pintype "bidirectional"))
    )
    (net (code "79") (name "unconnected-(IC1A-(AD7)PA7-Pad56)") (class "Default")
      (node (ref "IC1") (pin "56") (pinfunction "(AD7)PA7_56") (pintype "bidirectional"))
    )
    (net (code "80") (name "unconnected-(IC1A-(RXD0{slash}PCIN8)PE0-Pad31)") (class "Default")
      (node (ref "IC1") (pin "31") (pinfunction "(RXD0/PCIN8)PE0_31") (pintype "bidirectional"))
    )
    (net (code "81") (name "unconnected-(IC1A-(T0)PD7-Pad65)") (class "Default")
      (node (ref "IC1") (pin "65") (pinfunction "(T0)PD7_65") (pintype "bidirectional"))
    )
    (net (code "82") (name "unconnected-(IC1A-(TXD0)PE1-Pad32)") (class "Default")
      (node (ref "IC1") (pin "32") (pinfunction "(TXD0)PE1_32") (pintype "bidirectional"))
    )
    (net (code "83") (name "unconnected-(IC1A-PG0(~{WR})-Pad68)") (class "Default")
      (node (ref "IC1") (pin "68") (pinfunction "PG0(~{WR})_68") (pintype "bidirectional"))
    )
    (net (code "84") (name "unconnected-(IC1A-PG1(~{RD})-Pad67)") (class "Default")
      (node (ref "IC1") (pin "67") (pinfunction "PG1(~{RD})_67") (pintype "bidirectional"))
    )
    (net (code "85") (name "unconnected-(IC1A-PG2(ALE)-Pad66)") (class "Default")
      (node (ref "IC1") (pin "66") (pinfunction "PG2(ALE)_66") (pintype "bidirectional"))
    )
    (net (code "86") (name "unconnected-(IC1A-PG5(OC0B)-Pad35)") (class "Default")
      (node (ref "IC1") (pin "35") (pinfunction "PG5(OC0B)_35") (pintype "bidirectional"))
    )
    (net (code "87") (name "unconnected-(IC1A-PJ0(RXD3{slash}PCINT9)-Pad29)") (class "Default")
      (node (ref "IC1") (pin "29") (pinfunction "PJ0(RXD3/PCINT9)_29") (pintype "bidirectional"))
    )
    (net (code "88") (name "unconnected-(IC1A-PJ1(TXD3{slash}PCINT10)-Pad30)") (class "Default")
      (node (ref "IC1") (pin "30") (pinfunction "PJ1(TXD3/PCINT10)_30") (pintype "bidirectional"))
    )
    (net (code "89") (name "unconnected-(IC1A-PL0(ICP4)-Pad76)") (class "Default")
      (node (ref "IC1") (pin "76") (pinfunction "PL0(ICP4)_76") (pintype "bidirectional"))
    )
    (net (code "90") (name "unconnected-(IC1A-PL2(T5)-Pad74)") (class "Default")
      (node (ref "IC1") (pin "74") (pinfunction "PL2(T5)_74") (pintype "bidirectional"))
    )
    (net (code "91") (name "unconnected-(IC1A-PL3(OC5A)-Pad73)") (class "Default")
      (node (ref "IC1") (pin "73") (pinfunction "PL3(OC5A)_73") (pintype "bidirectional"))
    )
    (net (code "92") (name "unconnected-(IC1A-PL4(OC5B)-Pad72)") (class "Default")
      (node (ref "IC1") (pin "72") (pinfunction "PL4(OC5B)_72") (pintype "bidirectional"))
    )
    (net (code "93") (name "unconnected-(IC1A-PL5(OC5C)-Pad71)") (class "Default")
      (node (ref "IC1") (pin "71") (pinfunction "PL5(OC5C)_71") (pintype "bidirectional"))
    )
    (net (code "94") (name "unconnected-(IC1A-PL6-Pad70)") (class "Default")
      (node (ref "IC1") (pin "70") (pinfunction "PL6_70") (pintype "bidirectional"))
    )
    (net (code "95") (name "unconnected-(IC1A-PL7-Pad69)") (class "Default")
      (node (ref "IC1") (pin "69") (pinfunction "PL7_69") (pintype "bidirectional"))
    )
    (net (code "96") (name "unconnected-(IC1A-~{RESET}-Pad1)") (class "Default")
      (node (ref "IC1") (pin "1") (pinfunction "~{RESET}_1") (pintype "bidirectional"))
    )
    (net (code "97") (name "unconnected-(PWR-Pad4)") (class "Default")
      (node (ref "PWR") (pin "4") (pinfunction "4_4") (pintype "passive"))
    )
  )
)
